# bbb_db25_terminals_extension.net
KiCad netlist of a schematic drawn in Altium Designer
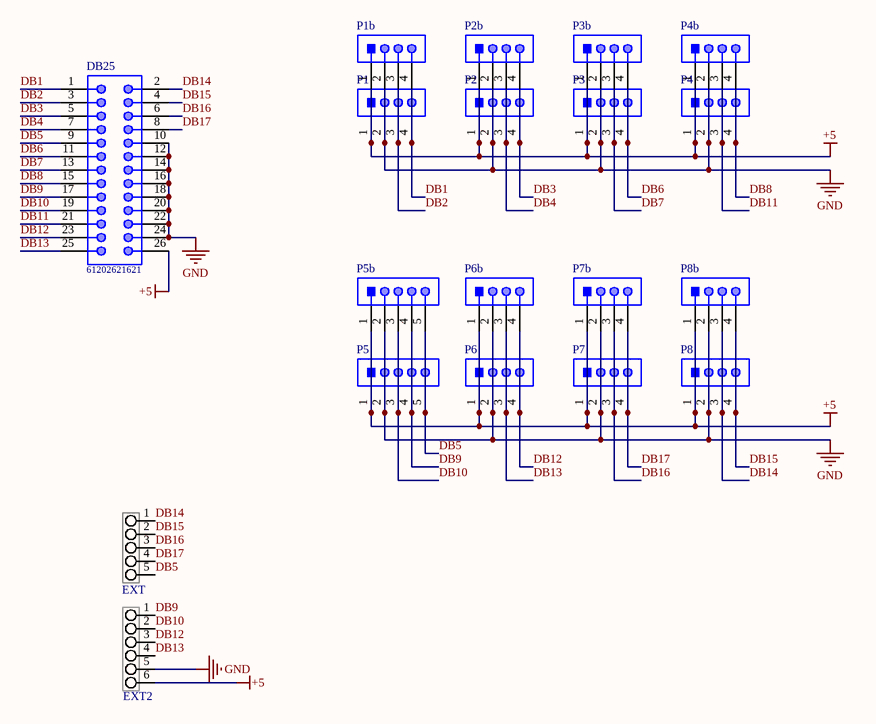
[diagram p0: bbb_db25_terminals_extension.SchDoc]

(export (version "E")
  (design (tool "Eeschema 10.0.6"))
  (components
    (comp (ref "DB25")
      (value "61202621621")
      (footprint "61202621621")
      (description "Male Box Header WR-BHD, THT, Vertical, pitch 2.54 mm, 26 pins")
      (fields (field (name "PUBLISHER") "Wurth Elektronik"))
      (libsource (lib "Altium_WR-BHD_rev19a") (part "61202621621"))
    )
    (comp (ref "EXT")
      (value "Header 1x5 compact")
      (footprint "Header 1x5 100mil Vertical")
      (description "Standard Header Connector")
      (libsource (lib "BB_Connectors") (part "Header 1x5 compact"))
    )
    (comp (ref "EXT2")
      (value "Header 1x6 compact")
      (footprint "Header 1x6 100mil Vertical")
      (description "Standard Header Connector")
      (libsource (lib "BB_Connectors") (part "Header 1x6 compact"))
    )
    (comp (ref "P1")
      (value "691322110004")
      (footprint "691322110004")
      (description "WR-TBL Serie 3221 Horizontal PCB Header, Pluggable, pitch 3.5mm, 4p")
      (fields (field (name "PUBLISHER") "Wurth Elektronik"))
      (libsource (lib "Altium_WR-TBL_rev19a") (part "691322110004"))
    )
    (comp (ref "P1b")
      (value "691321100004")
      (footprint "691321100004")
      (description "WR-TBL Serie 3211 Vertical PCB Header, Pluggable, pitch 3.5mm, 4p")
      (fields (field (name "PUBLISHER") "Wurth Elektronik"))
      (libsource (lib "Altium_WR-TBL_rev19a") (part "691321100004"))
    )
    (comp (ref "P2")
      (value "691322110004")
      (footprint "691322110004")
      (description "WR-TBL Serie 3221 Horizontal PCB Header, Pluggable, pitch 3.5mm, 4p")
      (fields (field (name "PUBLISHER") "Wurth Elektronik"))
      (libsource (lib "Altium_WR-TBL_rev19a") (part "691322110004"))
    )
    (comp (ref "P2b")
      (value "691321100004")
      (footprint "691321100004")
      (description "WR-TBL Serie 3211 Vertical PCB Header, Pluggable, pitch 3.5mm, 4p")
      (fields (field (name "PUBLISHER") "Wurth Elektronik"))
      (libsource (lib "Altium_WR-TBL_rev19a") (part "691321100004"))
    )
    (comp (ref "P3")
      (value "691322110004")
      (footprint "691322110004")
      (description "WR-TBL Serie 3221 Horizontal PCB Header, Pluggable, pitch 3.5mm, 4p")
      (fields (field (name "PUBLISHER") "Wurth Elektronik"))
      (libsource (lib "Altium_WR-TBL_rev19a") (part "691322110004"))
    )
    (comp (ref "P3b")
      (value "691321100004")
      (footprint "691321100004")
      (description "WR-TBL Serie 3211 Vertical PCB Header, Pluggable, pitch 3.5mm, 4p")
      (fields (field (name "PUBLISHER") "Wurth Elektronik"))
      (libsource (lib "Altium_WR-TBL_rev19a") (part "691321100004"))
    )
    (comp (ref "P4")
      (value "691322110004")
      (footprint "691322110004")
      (description "WR-TBL Serie 3221 Horizontal PCB Header, Pluggable, pitch 3.5mm, 4p")
      (fields (field (name "PUBLISHER") "Wurth Elektronik"))
      (libsource (lib "Altium_WR-TBL_rev19a") (part "691322110004"))
    )
    (comp (ref "P4b")
      (value "691321100004")
      (footprint "691321100004")
      (description "WR-TBL Serie 3211 Vertical PCB Header, Pluggable, pitch 3.5mm, 4p")
      (fields (field (name "PUBLISHER") "Wurth Elektronik"))
      (libsource (lib "Altium_WR-TBL_rev19a") (part "691321100004"))
    )
    (comp (ref "P5")
      (value "691322110005")
      (footprint "691322110005")
      (description "WR-TBL Serie 3221 Horizontal PCB Header, Pluggable, pitch 3.5mm, 5p")
      (fields (field (name "PUBLISHER") "Wurth Elektronik"))
      (libsource (lib "Altium_WR-TBL_rev19a") (part "691322110005"))
    )
    (comp (ref "P5b")
      (value "691321100005")
      (footprint "691321100005")
      (description "WR-TBL Serie 3211 Vertical PCB Header, Pluggable, pitch 3.5mm, 5p")
      (fields (field (name "PUBLISHER") "Wurth Elektronik"))
      (libsource (lib "Altium_WR-TBL_rev19a") (part "691321100005"))
    )
    (comp (ref "P6")
      (value "691322110004")
      (footprint "691322110004")
      (description "WR-TBL Serie 3221 Horizontal PCB Header, Pluggable, pitch 3.5mm, 4p")
      (fields (field (name "PUBLISHER") "Wurth Elektronik"))
      (libsource (lib "Altium_WR-TBL_rev19a") (part "691322110004"))
    )
    (comp (ref "P6b")
      (value "691321100004")
      (footprint "691321100004")
      (description "WR-TBL Serie 3211 Vertical PCB Header, Pluggable, pitch 3.5mm, 4p")
      (fields (field (name "PUBLISHER") "Wurth Elektronik"))
      (libsource (lib "Altium_WR-TBL_rev19a") (part "691321100004"))
    )
    (comp (ref "P7")
      (value "691322110004")
      (footprint "691322110004")
      (description "WR-TBL Serie 3221 Horizontal PCB Header, Pluggable, pitch 3.5mm, 4p")
      (fields (field (name "PUBLISHER") "Wurth Elektronik"))
      (libsource (lib "Altium_WR-TBL_rev19a") (part "691322110004"))
    )
    (comp (ref "P7b")
      (value "691321100004")
      (footprint "691321100004")
      (description "WR-TBL Serie 3211 Vertical PCB Header, Pluggable, pitch 3.5mm, 4p")
      (fields (field (name "PUBLISHER") "Wurth Elektronik"))
      (libsource (lib "Altium_WR-TBL_rev19a") (part "691321100004"))
    )
    (comp (ref "P8")
      (value "691322110004")
      (footprint "691322110004")
      (description "WR-TBL Serie 3221 Horizontal PCB Header, Pluggable, pitch 3.5mm, 4p")
      (fields (field (name "PUBLISHER") "Wurth Elektronik"))
      (libsource (lib "Altium_WR-TBL_rev19a") (part "691322110004"))
    )
    (comp (ref "P8b")
      (value "691321100004")
      (footprint "691321100004")
      (description "WR-TBL Serie 3211 Vertical PCB Header, Pluggable, pitch 3.5mm, 4p")
      (fields (field (name "PUBLISHER") "Wurth Elektronik"))
      (libsource (lib "Altium_WR-TBL_rev19a") (part "691321100004"))
    )
  )
  (nets
    (net (code "1") (name "+5") (class "Default")
      (node (ref "DB25") (pin "26") (pinfunction "26_26") (pintype "passive"))
      (node (ref "EXT2") (pin "6") (pinfunction "6_6") (pintype "passive"))
      (node (ref "P1") (pin "1") (pinfunction "1_1") (pintype "passive"))
      (node (ref "P1b") (pin "1") (pinfunction "1_1") (pintype "passive"))
      (node (ref "P2") (pin "1") (pinfunction "1_1") (pintype "passive"))
      (node (ref "P2b") (pin "1") (pinfunction "1_1") (pintype "passive"))
      (node (ref "P3") (pin "1") (pinfunction "1_1") (pintype "passive"))
      (node (ref "P3b") (pin "1") (pinfunction "1_1") (pintype "passive"))
      (node (ref "P4") (pin "1") (pinfunction "1_1") (pintype "passive"))
      (node (ref "P4b") (pin "1") (pinfunction "1_1") (pintype "passive"))
      (node (ref "P5") (pin "1") (pinfunction "1_1") (pintype "passive"))
      (node (ref "P5b") (pin "1") (pinfunction "1_1") (pintype "passive"))
      (node (ref "P6") (pin "1") (pinfunction "1_1") (pintype "passive"))
      (node (ref "P6b") (pin "1") (pinfunction "1_1") (pintype "passive"))
      (node (ref "P7") (pin "1") (pinfunction "1_1") (pintype "passive"))
      (node (ref "P7b") (pin "1") (pinfunction "1_1") (pintype "passive"))
      (node (ref "P8") (pin "1") (pinfunction "1_1") (pintype "passive"))
      (node (ref "P8b") (pin "1") (pinfunction "1_1") (pintype "passive"))
    )
    (net (code "2") (name "/DB1") (class "Default")
      (node (ref "DB25") (pin "1") (pinfunction "1_1") (pintype "passive"))
      (node (ref "P1") (pin "4") (pinfunction "4_4") (pintype "passive"))
      (node (ref "P1b") (pin "4") (pinfunction "4_4") (pintype "passive"))
    )
    (net (code "3") (name "/DB2") (class "Default")
      (node (ref "DB25") (pin "3") (pinfunction "3_3") (pintype "passive"))
      (node (ref "P1") (pin "3") (pinfunction "3_3") (pintype "passive"))
      (node (ref "P1b") (pin "3") (pinfunction "3_3") (pintype "passive"))
    )
    (net (code "4") (name "/DB3") (class "Default")
      (node (ref "DB25") (pin "5") (pinfunction "5_5") (pintype "passive"))
      (node (ref "P2") (pin "4") (pinfunction "4_4") (pintype "passive"))
      (node (ref "P2b") (pin "4") (pinfunction "4_4") (pintype "passive"))
    )
    (net (code "5") (name "/DB4") (class "Default")
      (node (ref "DB25") (pin "7") (pinfunction "7_7") (pintype "passive"))
      (node (ref "P2") (pin "3") (pinfunction "3_3") (pintype "passive"))
      (node (ref "P2b") (pin "3") (pinfunction "3_3") (pintype "passive"))
    )
    (net (code "6") (name "/DB5") (class "Default")
      (node (ref "DB25") (pin "9") (pinfunction "9_9") (pintype "passive"))
      (node (ref "EXT") (pin "5") (pinfunction "5_5") (pintype "passive"))
      (node (ref "P5") (pin "5") (pinfunction "5_5") (pintype "passive"))
      (node (ref "P5b") (pin "5") (pinfunction "5_5") (pintype "passive"))
    )
    (net (code "7") (name "/DB6") (class "Default")
      (node (ref "DB25") (pin "11") (pinfunction "11_11") (pintype "passive"))
      (node (ref "P3") (pin "4") (pinfunction "4_4") (pintype "passive"))
      (node (ref "P3b") (pin "4") (pinfunction "4_4") (pintype "passive"))
    )
    (net (code "8") (name "/DB7") (class "Default")
      (node (ref "DB25") (pin "13") (pinfunction "13_13") (pintype "passive"))
      (node (ref "P3") (pin "3") (pinfunction "3_3") (pintype "passive"))
      (node (ref "P3b") (pin "3") (pinfunction "3_3") (pintype "passive"))
    )
    (net (code "9") (name "/DB8") (class "Default")
      (node (ref "DB25") (pin "15") (pinfunction "15_15") (pintype "passive"))
      (node (ref "P4") (pin "4") (pinfunction "4_4") (pintype "passive"))
      (node (ref "P4b") (pin "4") (pinfunction "4_4") (pintype "passive"))
    )
    (net (code "10") (name "/DB9") (class "Default")
      (node (ref "DB25") (pin "17") (pinfunction "17_17") (pintype "passive"))
      (node (ref "EXT2") (pin "1") (pinfunction "1_1") (pintype "passive"))
      (node (ref "P5") (pin "4") (pinfunction "4_4") (pintype "passive"))
      (node (ref "P5b") (pin "4") (pinfunction "4_4") (pintype "passive"))
    )
    (net (code "11") (name "/DB10") (class "Default")
      (node (ref "DB25") (pin "19") (pinfunction "19_19") (pintype "passive"))
      (node (ref "EXT2") (pin "2") (pinfunction "2_2") (pintype "passive"))
      (node (ref "P5") (pin "3") (pinfunction "3_3") (pintype "passive"))
      (node (ref "P5b") (pin "3") (pinfunction "3_3") (pintype "passive"))
    )
    (net (code "12") (name "/DB11") (class "Default")
      (node (ref "DB25") (pin "21") (pinfunction "21_21") (pintype "passive"))
      (node (ref "P4") (pin "3") (pinfunction "3_3") (pintype "passive"))
      (node (ref "P4b") (pin "3") (pinfunction "3_3") (pintype "passive"))
    )
    (net (code "13") (name "/DB12") (class "Default")
      (node (ref "DB25") (pin "23") (pinfunction "23_23") (pintype "passive"))
      (node (ref "EXT2") (pin "3") (pinfunction "3_3") (pintype "passive"))
      (node (ref "P6") (pin "4") (pinfunction "4_4") (pintype "passive"))
      (node (ref "P6b") (pin "4") (pinfunction "4_4") (pintype "passive"))
    )
    (net (code "14") (name "/DB13") (class "Default")
      (node (ref "DB25") (pin "25") (pinfunction "25_25") (pintype "passive"))
      (node (ref "EXT2") (pin "4") (pinfunction "4_4") (pintype "passive"))
      (node (ref "P6") (pin "3") (pinfunction "3_3") (pintype "passive"))
      (node (ref "P6b") (pin "3") (pinfunction "3_3") (pintype "passive"))
    )
    (net (code "15") (name "/DB14") (class "Default")
      (node (ref "DB25") (pin "2") (pinfunction "2_2") (pintype "passive"))
      (node (ref "EXT") (pin "1") (pinfunction "1_1") (pintype "passive"))
      (node (ref "P8") (pin "3") (pinfunction "3_3") (pintype "passive"))
      (node (ref "P8b") (pin "3") (pinfunction "3_3") (pintype "passive"))
    )
    (net (code "16") (name "/DB15") (class "Default")
      (node (ref "DB25") (pin "4") (pinfunction "4_4") (pintype "passive"))
      (node (ref "EXT") (pin "2") (pinfunction "2_2") (pintype "passive"))
      (node (ref "P8") (pin "4") (pinfunction "4_4") (pintype "passive"))
      (node (ref "P8b") (pin "4") (pinfunction "4_4") (pintype "passive"))
    )
    (net (code "17") (name "/DB16") (class "Default")
      (node (ref "DB25") (pin "6") (pinfunction "6_6") (pintype "passive"))
      (node (ref "EXT") (pin "3") (pinfunction "3_3") (pintype "passive"))
      (node (ref "P7") (pin "3") (pinfunction "3_3") (pintype "passive"))
      (node (ref "P7b") (pin "3") (pinfunction "3_3") (pintype "passive"))
    )
    (net (code "18") (name "/DB17") (class "Default")
      (node (ref "DB25") (pin "8") (pinfunction "8_8") (pintype "passive"))
      (node (ref "EXT") (pin "4") (pinfunction "4_4") (pintype "passive"))
      (node (ref "P7") (pin "4") (pinfunction "4_4") (pintype "passive"))
      (node (ref "P7b") (pin "4") (pinfunction "4_4") (pintype "passive"))
    )
    (net (code "19") (name "GND") (class "Default")
      (node (ref "DB25") (pin "10") (pinfunction "10_10") (pintype "passive"))
      (node (ref "DB25") (pin "12") (pinfunction "12_12") (pintype "passive"))
      (node (ref "DB25") (pin "14") (pinfunction "14_14") (pintype "passive"))
      (node (ref "DB25") (pin "16") (pinfunction "16_16") (pintype "passive"))
      (node (ref "DB25") (pin "18") (pinfunction "18_18") (pintype "passive"))
      (node (ref "DB25") (pin "20") (pinfunction "20_20") (pintype "passive"))
      (node (ref "DB25") (pin "22") (pinfunction "22_22") (pintype "passive"))
      (node (ref "DB25") (pin "24") (pinfunction "24_24") (pintype "passive"))
      (node (ref "EXT2") (pin "5") (pinfunction "5_5") (pintype "passive"))
      (node (ref "P1") (pin "2") (pinfunction "2_2") (pintype "passive"))
      (node (ref "P1b") (pin "2") (pinfunction "2_2") (pintype "passive"))
      (node (ref "P2") (pin "2") (pinfunction "2_2") (pintype "passive"))
      (node (ref "P2b") (pin "2") (pinfunction "2_2") (pintype "passive"))
      (node (ref "P3") (pin "2") (pinfunction "2_2") (pintype "passive"))
      (node (ref "P3b") (pin "2") (pinfunction "2_2") (pintype "passive"))
      (node (ref "P4") (pin "2") (pinfunction "2_2") (pintype "passive"))
      (node (ref "P4b") (pin "2") (pinfunction "2_2") (pintype "passive"))
      (node (ref "P5") (pin "2") (pinfunction "2_2") (pintype "passive"))
      (node (ref "P5b") (pin "2") (pinfunction "2_2") (pintype "passive"))
      (node (ref "P6") (pin "2") (pinfunction "2_2") (pintype "passive"))
      (node (ref "P6b") (pin "2") (pinfunction "2_2") (pintype "passive"))
      (node (ref "P7") (pin "2") (pinfunction "2_2") (pintype "passive"))
      (node (ref "P7b") (pin "2") (pinfunction "2_2") (pintype "passive"))
      (node (ref "P8") (pin "2") (pinfunction "2_2") (pintype "passive"))
      (node (ref "P8b") (pin "2") (pinfunction "2_2") (pintype "passive"))
    )
  )
)
